# ESP32C3_VOICE_LED_WS2812B_Sheet.net
KiCad netlist of a schematic drawn in Altium Designer
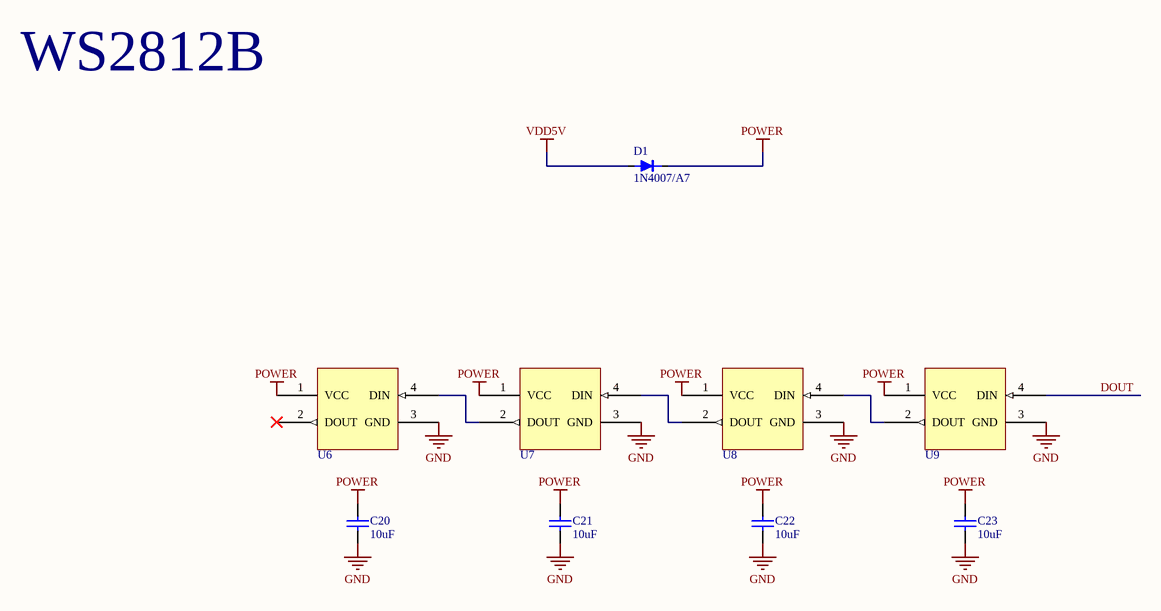
[diagram p0: ESP32C3_VOICE_LED_WS2812B_Sheet.SchDoc]

(export (version "E")
  (design (tool "Eeschema 10.0.6"))
  (components
    (comp (ref "C20")
      (value "10uF")
      (footprint "0603")
      (description "Capacitor")
      (fields (field (name "Comment") "Cap") (field (name "PUBLISHER") "Altium Limited"))
      (libsource (lib "CORE_COMPONENT") (part "Cap"))
    )
    (comp (ref "C21")
      (value "10uF")
      (footprint "0603")
      (description "Capacitor")
      (fields (field (name "Comment") "Cap") (field (name "PUBLISHER") "Altium Limited"))
      (libsource (lib "CORE_COMPONENT") (part "Cap"))
    )
    (comp (ref "C22")
      (value "10uF")
      (footprint "0603")
      (description "Capacitor")
      (fields (field (name "Comment") "Cap") (field (name "PUBLISHER") "Altium Limited"))
      (libsource (lib "CORE_COMPONENT") (part "Cap"))
    )
    (comp (ref "C23")
      (value "10uF")
      (footprint "0603")
      (description "Capacitor")
      (fields (field (name "Comment") "Cap") (field (name "PUBLISHER") "Altium Limited"))
      (libsource (lib "CORE_COMPONENT") (part "Cap"))
    )
    (comp (ref "D1")
      (value "1N4007/A7")
      (footprint "SOD-123FL")
      (libsource (lib "CORE_COMPONENT") (part "DIODE"))
    )
    (comp (ref "U6") (value "WS2812B") (footprint "5050") (libsource (lib "CORE_COMPONENT") (part "WS2812B")))
    (comp (ref "U7") (value "WS2812B") (footprint "5050") (libsource (lib "CORE_COMPONENT") (part "WS2812B")))
    (comp (ref "U8") (value "WS2812B") (footprint "5050") (libsource (lib "CORE_COMPONENT") (part "WS2812B")))
    (comp (ref "U9") (value "WS2812B") (footprint "5050") (libsource (lib "CORE_COMPONENT") (part "WS2812B")))
  )
  (nets
    (net (code "1") (name "/DOUT") (class "Default")
      (node (ref "U9") (pin "4") (pinfunction "DIN_4") (pintype "input"))
    )
    (net (code "2") (name "GND") (class "Default")
      (node (ref "C20") (pin "2") (pinfunction "2_2") (pintype "passive"))
      (node (ref "C21") (pin "2") (pinfunction "2_2") (pintype "passive"))
      (node (ref "C22") (pin "2") (pinfunction "2_2") (pintype "passive"))
      (node (ref "C23") (pin "2") (pinfunction "2_2") (pintype "passive"))
      (node (ref "U6") (pin "3") (pinfunction "GND_3") (pintype "power_in"))
      (node (ref "U7") (pin "3") (pinfunction "GND_3") (pintype "power_in"))
      (node (ref "U8") (pin "3") (pinfunction "GND_3") (pintype "power_in"))
      (node (ref "U9") (pin "3") (pinfunction "GND_3") (pintype "power_in"))
    )
    (net (code "3") (name "Net-(U6-DIN)") (class "Default")
      (node (ref "U6") (pin "4") (pinfunction "DIN_4") (pintype "input"))
      (node (ref "U7") (pin "2") (pinfunction "DOUT_2") (pintype "output"))
    )
    (net (code "4") (name "Net-(U7-DIN)") (class "Default")
      (node (ref "U7") (pin "4") (pinfunction "DIN_4") (pintype "input"))
      (node (ref "U8") (pin "2") (pinfunction "DOUT_2") (pintype "output"))
    )
    (net (code "5") (name "Net-(U8-DIN)") (class "Default")
      (node (ref "U8") (pin "4") (pinfunction "DIN_4") (pintype "input"))
      (node (ref "U9") (pin "2") (pinfunction "DOUT_2") (pintype "output"))
    )
    (net (code "6") (name "POWER") (class "Default")
      (node (ref "C20") (pin "1") (pinfunction "1_1") (pintype "passive"))
      (node (ref "C21") (pin "1") (pinfunction "1_1") (pintype "passive"))
      (node (ref "C22") (pin "1") (pinfunction "1_1") (pintype "passive"))
      (node (ref "C23") (pin "1") (pinfunction "1_1") (pintype "passive"))
      (node (ref "D1") (pin "K") (pinfunction "K_K") (pintype "passive"))
      (node (ref "U6") (pin "1") (pinfunction "VCC_1") (pintype "power_in"))
      (node (ref "U7") (pin "1") (pinfunction "VCC_1") (pintype "power_in"))
      (node (ref "U8") (pin "1") (pinfunction "VCC_1") (pintype "power_in"))
      (node (ref "U9") (pin "1") (pinfunction "VCC_1") (pintype "power_in"))
    )
    (net (code "7") (name "VDD5V") (class "Default")
      (node (ref "D1") (pin "A") (pinfunction "A_A") (pintype "passive"))
    )
    (net (code "8") (name "unconnected-(U6-DOUT-Pad2)") (class "Default")
      (node (ref "U6") (pin "2") (pinfunction "DOUT_2") (pintype "output+no_connect"))
    )
  )
)
